# ZENER_DIODE_TESTER.net
KiCad netlist of a schematic drawn in EAGLE
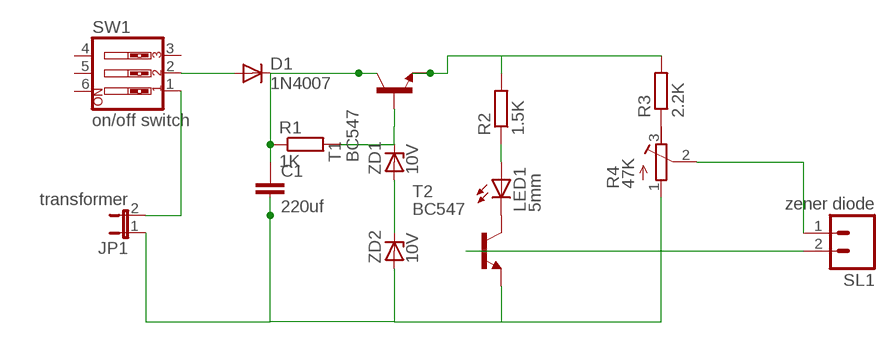
[diagram p0: schematic, sheet 1]

(export (version "E")
  (design (tool "Eeschema 10.0.6"))
  (components
    (comp (ref "C1")
      (value "220uf")
      (footprint "eagle-import:C2.5-6")
      (libsource (lib "eagle-import") (part "C2.5/6"))
    )
    (comp (ref "D1")
      (value "1N4007")
      (footprint "eagle-import:DO41-10")
      (libsource (lib "eagle-import") (part "1N4004"))
    )
    (comp (ref "JP1")
      (value "transformer")
      (footprint "eagle-import:JP1")
      (libsource (lib "eagle-import") (part "JP1E"))
    )
    (comp (ref "LED1")
      (value "5mm")
      (footprint "eagle-import:LED5MM")
      (libsource (lib "eagle-import") (part "LED5MM"))
    )
    (comp (ref "R1")
      (value "1K")
      (footprint "eagle-import:0204_7")
      (libsource (lib "eagle-import") (part "R-EU_0204/7"))
    )
    (comp (ref "R2")
      (value "1.5K")
      (footprint "eagle-import:0204_7")
      (libsource (lib "eagle-import") (part "R-EU_0204/7"))
    )
    (comp (ref "R3")
      (value "2.2K")
      (footprint "eagle-import:0204_7")
      (libsource (lib "eagle-import") (part "R-EU_0204/7"))
    )
    (comp (ref "R4")
      (value "47K")
      (footprint "eagle-import:RTRIM64P")
      (libsource (lib "eagle-import") (part "R-TRIMM64P"))
    )
    (comp (ref "SL1")
      (value "zener diode")
      (footprint "eagle-import:02P")
      (libsource (lib "eagle-import") (part "M02"))
    )
    (comp (ref "SW1")
      (value "on/off switch")
      (footprint "eagle-import:EDG-03")
      (libsource (lib "eagle-import") (part "SW_DIP-3"))
    )
    (comp (ref "T1")
      (value "BC547")
      (footprint "eagle-import:TO92")
      (libsource (lib "eagle-import") (part "BC547"))
    )
    (comp (ref "T2")
      (value "BC547")
      (footprint "eagle-import:TO92")
      (libsource (lib "eagle-import") (part "BC547"))
    )
    (comp (ref "ZD1")
      (value "10V")
      (footprint "eagle-import:DO35Z10")
      (libsource (lib "eagle-import") (part "ZPD"))
    )
    (comp (ref "ZD2")
      (value "10V")
      (footprint "eagle-import:DO35Z10")
      (libsource (lib "eagle-import") (part "ZPD"))
    )
  )
  (nets
    (net (code "1") (name "Net-(D1-PadA)") (class "Default")
      (node (ref "D1") (pin "A") (pinfunction "A_A") (pintype "passive"))
      (node (ref "SW1") (pin "2") (pinfunction "2_2") (pintype "passive"))
    )
    (net (code "2") (name "Net-(JP1-Pad2)") (class "Default")
      (node (ref "JP1") (pin "2") (pinfunction "2_2") (pintype "passive"))
      (node (ref "SW1") (pin "1") (pinfunction "1_1") (pintype "passive"))
    )
    (net (code "3") (name "Net-(LED1-C)") (class "Default")
      (node (ref "LED1") (pin "K") (pinfunction "C_K") (pintype "passive"))
      (node (ref "T2") (pin "3") (pinfunction "C_3") (pintype "passive"))
    )
    (net (code "4") (name "Net-(LED1-PadA)") (class "Default")
      (node (ref "LED1") (pin "A") (pinfunction "A_A") (pintype "passive"))
      (node (ref "R2") (pin "1") (pinfunction "1_1") (pintype "passive"))
    )
    (net (code "5") (name "Net-(R4-A)") (class "Default")
      (node (ref "R3") (pin "1") (pinfunction "1_1") (pintype "passive"))
      (node (ref "R4") (pin "3") (pinfunction "A_3") (pintype "passive"))
    )
    (net (code "6") (name "Net-(R4-E)") (class "Default")
      (node (ref "C1") (pin "2") (pinfunction "2_2") (pintype "passive"))
      (node (ref "JP1") (pin "1") (pinfunction "1_1") (pintype "passive"))
      (node (ref "R4") (pin "1") (pinfunction "E_1") (pintype "passive"))
      (node (ref "T2") (pin "1") (pinfunction "E_1") (pintype "passive"))
      (node (ref "ZD2") (pin "A") (pinfunction "A_A") (pintype "passive"))
    )
    (net (code "7") (name "Net-(R4-S)") (class "Default")
      (node (ref "R4") (pin "2") (pinfunction "S_2") (pintype "passive"))
      (node (ref "SL1") (pin "1") (pinfunction "1_1") (pintype "passive"))
    )
    (net (code "8") (name "Net-(T1-B)") (class "Default")
      (node (ref "R1") (pin "2") (pinfunction "2_2") (pintype "passive"))
      (node (ref "T1") (pin "2") (pinfunction "B_2") (pintype "passive"))
      (node (ref "ZD1") (pin "C") (pinfunction "C_C") (pintype "passive"))
    )
    (net (code "9") (name "Net-(T1-C)") (class "Default")
      (node (ref "C1") (pin "1") (pinfunction "1_1") (pintype "passive"))
      (node (ref "D1") (pin "C") (pinfunction "C_C") (pintype "passive"))
      (node (ref "R1") (pin "1") (pinfunction "1_1") (pintype "passive"))
      (node (ref "T1") (pin "3") (pinfunction "C_3") (pintype "passive"))
    )
    (net (code "10") (name "Net-(T1-E)") (class "Default")
      (node (ref "R2") (pin "2") (pinfunction "2_2") (pintype "passive"))
      (node (ref "R3") (pin "2") (pinfunction "2_2") (pintype "passive"))
      (node (ref "T1") (pin "1") (pinfunction "E_1") (pintype "passive"))
    )
    (net (code "11") (name "Net-(T2-B)") (class "Default")
      (node (ref "SL1") (pin "2") (pinfunction "2_2") (pintype "passive"))
      (node (ref "T2") (pin "2") (pinfunction "B_2") (pintype "passive"))
    )
    (net (code "12") (name "Net-(ZD1-PadA)") (class "Default")
      (node (ref "ZD1") (pin "A") (pinfunction "A_A") (pintype "passive"))
      (node (ref "ZD2") (pin "C") (pinfunction "C_C") (pintype "passive"))
    )
    (net (code "13") (name "unconnected-(SW1-Pad3)") (class "Default")
      (node (ref "SW1") (pin "3") (pinfunction "3_3") (pintype "passive"))
    )
    (net (code "14") (name "unconnected-(SW1-Pad4)") (class "Default")
      (node (ref "SW1") (pin "4") (pinfunction "4_4") (pintype "passive"))
    )
    (net (code "15") (name "unconnected-(SW1-Pad5)") (class "Default")
      (node (ref "SW1") (pin "5") (pinfunction "5_5") (pintype "passive"))
    )
    (net (code "16") (name "unconnected-(SW1-Pad6)") (class "Default")
      (node (ref "SW1") (pin "6") (pinfunction "6_6") (pintype "passive"))
    )
  )
)
